# boxer_spliter.net
KiCad netlist of a schematic drawn in Altium Designer
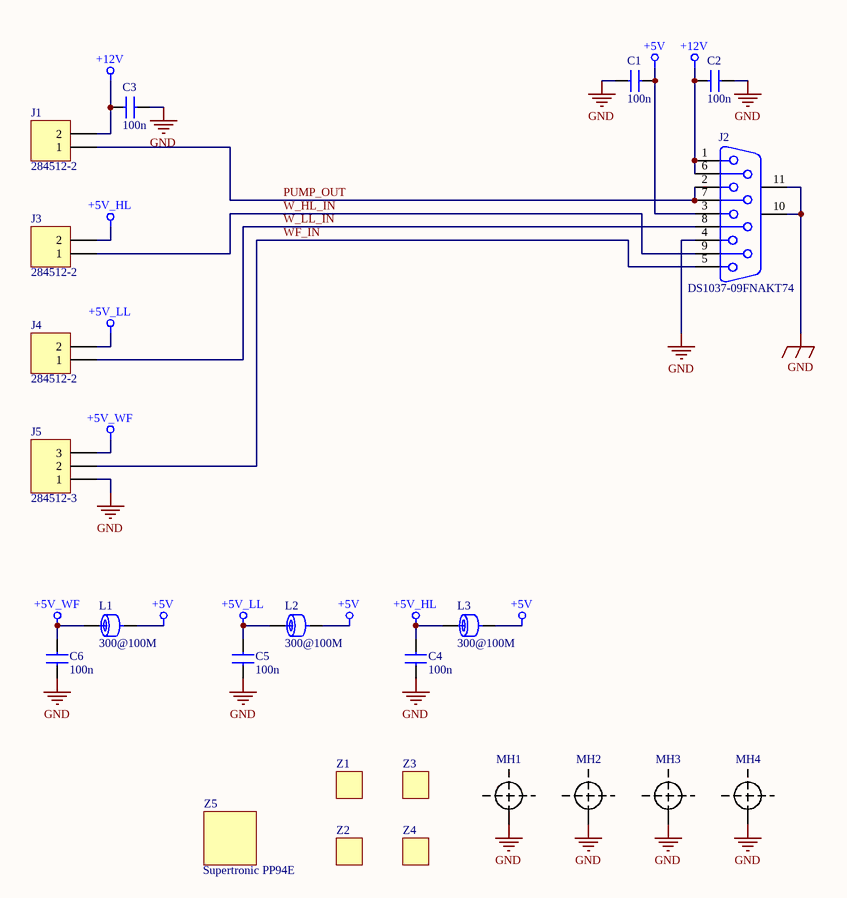
[diagram p0: boxer_spliter.SchDoc]

(export (version "E")
  (design (tool "Eeschema 10.0.6"))
  (components
    (comp (ref "C1")
      (value "100n")
      (footprint "C_0805")
      (description "Capacitor")
      (libsource (lib "boxer_pas") (part "Capacitor"))
    )
    (comp (ref "C2")
      (value "100n")
      (footprint "C_0805")
      (description "Capacitor")
      (libsource (lib "boxer_pas") (part "Capacitor"))
    )
    (comp (ref "C3")
      (value "100n")
      (footprint "C_0805")
      (description "Capacitor")
      (libsource (lib "boxer_pas") (part "Capacitor"))
    )
    (comp (ref "C4")
      (value "100n")
      (footprint "C_0805")
      (description "Capacitor")
      (libsource (lib "boxer_pas") (part "Capacitor"))
    )
    (comp (ref "C5")
      (value "100n")
      (footprint "C_0805")
      (description "Capacitor")
      (libsource (lib "boxer_pas") (part "Capacitor"))
    )
    (comp (ref "C6")
      (value "100n")
      (footprint "C_0805")
      (description "Capacitor")
      (libsource (lib "boxer_pas") (part "Capacitor"))
    )
    (comp (ref "J1")
      (value "284512-2")
      (footprint "284512-2")
      (description "Header, 2-Pin")
      (libsource (lib "boxer_mechanical") (part "Header 2"))
    )
    (comp (ref "J2")
      (value "DS1037-09FNAKT74")
      (footprint "DB9")
      (description "Receptacle Assembly, 9 Position, Right Angle")
      (libsource (lib "boxer_mechanical") (part "DB9"))
    )
    (comp (ref "J3")
      (value "284512-2")
      (footprint "284512-2")
      (description "Header, 2-Pin")
      (libsource (lib "boxer_mechanical") (part "Header 2"))
    )
    (comp (ref "J4")
      (value "284512-2")
      (footprint "284512-2")
      (description "Header, 2-Pin")
      (libsource (lib "boxer_mechanical") (part "Header 2"))
    )
    (comp (ref "J5")
      (value "284512-3")
      (footprint "284512-3")
      (description "Header, 3-Pin")
      (libsource (lib "boxer_mechanical") (part "Header 3"))
    )
    (comp (ref "L1")
      (value "300@100M")
      (footprint "L_0805")
      (description "Ferrite Bead")
      (fields (field (name "Comment") "742792031"))
      (libsource (lib "boxer_pas") (part "FB"))
    )
    (comp (ref "L2")
      (value "300@100M")
      (footprint "L_0805")
      (description "Ferrite Bead")
      (fields (field (name "Comment") "742792031"))
      (libsource (lib "boxer_pas") (part "FB"))
    )
    (comp (ref "L3")
      (value "300@100M")
      (footprint "L_0805")
      (description "Ferrite Bead")
      (fields (field (name "Comment") "742792031"))
      (libsource (lib "boxer_pas") (part "FB"))
    )
    (comp (ref "MH1")
      (value "Mounting hole")
      (footprint "MH_M3")
      (description "Mounting hole 2.3mm")
      (libsource (lib "boxer_mechanical") (part "Mounting hole"))
    )
    (comp (ref "MH2")
      (value "Mounting hole")
      (footprint "MH_M3")
      (description "Mounting hole 2.3mm")
      (libsource (lib "boxer_mechanical") (part "Mounting hole"))
    )
    (comp (ref "MH3")
      (value "Mounting hole")
      (footprint "MH_M3")
      (description "Mounting hole 2.3mm")
      (libsource (lib "boxer_mechanical") (part "Mounting hole"))
    )
    (comp (ref "MH4")
      (value "Mounting hole")
      (footprint "MH_M3")
      (description "Mounting hole 2.3mm")
      (libsource (lib "boxer_mechanical") (part "Mounting hole"))
    )
    (comp (ref "Z1")
      (value "Hexagonal M3 5mm spacer")
      (footprint "SPACER_M3_5mm")
      (libsource (lib "boxer_mechanical") (part "SPACER_M3_5mm"))
    )
    (comp (ref "Z2")
      (value "Hexagonal M3 5mm spacer")
      (footprint "SPACER_M3_5mm")
      (libsource (lib "boxer_mechanical") (part "SPACER_M3_5mm"))
    )
    (comp (ref "Z3")
      (value "Hexagonal M3 5mm spacer")
      (footprint "SPACER_M3_5mm")
      (libsource (lib "boxer_mechanical") (part "SPACER_M3_5mm"))
    )
    (comp (ref "Z4")
      (value "Hexagonal M3 5mm spacer")
      (footprint "SPACER_M3_5mm")
      (libsource (lib "boxer_mechanical") (part "SPACER_M3_5mm"))
    )
    (comp (ref "Z5")
      (value "Supertronic PP94E")
      (footprint "PP94E")
      (libsource (lib "boxer_mechanical") (part "PP94E"))
    )
  )
  (nets
    (net (code "1") (name "+5V") (class "Default")
      (node (ref "C1") (pin "1") (pinfunction "1_1") (pintype "passive"))
      (node (ref "J2") (pin "3") (pinfunction "3_3") (pintype "passive"))
      (node (ref "L1") (pin "2") (pinfunction "2_2") (pintype "passive"))
      (node (ref "L2") (pin "2") (pinfunction "2_2") (pintype "passive"))
      (node (ref "L3") (pin "2") (pinfunction "2_2") (pintype "passive"))
    )
    (net (code "2") (name "+5V_HL") (class "Default")
      (node (ref "C4") (pin "1") (pinfunction "1_1") (pintype "passive"))
      (node (ref "J3") (pin "2") (pinfunction "2_2") (pintype "passive"))
      (node (ref "L3") (pin "1") (pinfunction "1_1") (pintype "passive"))
    )
    (net (code "3") (name "+5V_LL") (class "Default")
      (node (ref "C5") (pin "1") (pinfunction "1_1") (pintype "passive"))
      (node (ref "J4") (pin "2") (pinfunction "2_2") (pintype "passive"))
      (node (ref "L2") (pin "1") (pinfunction "1_1") (pintype "passive"))
    )
    (net (code "4") (name "+5V_WF") (class "Default")
      (node (ref "C6") (pin "1") (pinfunction "1_1") (pintype "passive"))
      (node (ref "J5") (pin "3") (pinfunction "3_3") (pintype "passive"))
      (node (ref "L1") (pin "1") (pinfunction "1_1") (pintype "passive"))
    )
    (net (code "5") (name "+12V") (class "Default")
      (node (ref "C2") (pin "1") (pinfunction "1_1") (pintype "passive"))
      (node (ref "C3") (pin "1") (pinfunction "1_1") (pintype "passive"))
      (node (ref "J1") (pin "2") (pinfunction "2_2") (pintype "passive"))
      (node (ref "J2") (pin "1") (pinfunction "1_1") (pintype "passive"))
      (node (ref "J2") (pin "6") (pinfunction "6_6") (pintype "passive"))
    )
    (net (code "6") (name "/PUMP_OUT") (class "Default")
      (node (ref "J1") (pin "1") (pinfunction "1_1") (pintype "passive"))
      (node (ref "J2") (pin "2") (pinfunction "2_2") (pintype "passive"))
      (node (ref "J2") (pin "7") (pinfunction "7_7") (pintype "passive"))
    )
    (net (code "7") (name "/WF_IN") (class "Default")
      (node (ref "J2") (pin "5") (pinfunction "5_5") (pintype "passive"))
      (node (ref "J5") (pin "2") (pinfunction "2_2") (pintype "passive"))
    )
    (net (code "8") (name "/W_HL_IN") (class "Default")
      (node (ref "J2") (pin "9") (pinfunction "9_9") (pintype "passive"))
      (node (ref "J3") (pin "1") (pinfunction "1_1") (pintype "passive"))
    )
    (net (code "9") (name "/W_LL_IN") (class "Default")
      (node (ref "J2") (pin "8") (pinfunction "8_8") (pintype "passive"))
      (node (ref "J4") (pin "1") (pinfunction "1_1") (pintype "passive"))
    )
    (net (code "10") (name "GND") (class "Default")
      (node (ref "C1") (pin "2") (pinfunction "2_2") (pintype "passive"))
      (node (ref "C2") (pin "2") (pinfunction "2_2") (pintype "passive"))
      (node (ref "C3") (pin "2") (pinfunction "2_2") (pintype "passive"))
      (node (ref "C4") (pin "2") (pinfunction "2_2") (pintype "passive"))
      (node (ref "C5") (pin "2") (pinfunction "2_2") (pintype "passive"))
      (node (ref "C6") (pin "2") (pinfunction "2_2") (pintype "passive"))
      (node (ref "J2") (pin "10") (pinfunction "MH1_10") (pintype "passive"))
      (node (ref "J2") (pin "11") (pinfunction "MH2_11") (pintype "passive"))
      (node (ref "J2") (pin "4") (pinfunction "4_4") (pintype "passive"))
      (node (ref "J5") (pin "1") (pinfunction "1_1") (pintype "passive"))
      (node (ref "MH1") (pin "MH") (pinfunction "MH_MH") (pintype "passive"))
      (node (ref "MH2") (pin "MH") (pinfunction "MH_MH") (pintype "passive"))
      (node (ref "MH3") (pin "MH") (pinfunction "MH_MH") (pintype "passive"))
      (node (ref "MH4") (pin "MH") (pinfunction "MH_MH") (pintype "passive"))
    )
  )
)
